# USB.net
KiCad netlist of a schematic drawn in Altium Designer
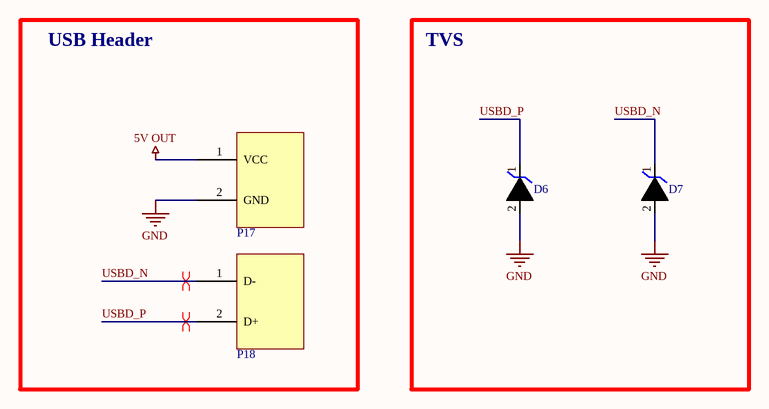
[diagram p0: USB.SchDoc]

(export (version "E")
  (design (tool "Eeschema 10.0.6"))
  (components
    (comp (ref "D6")
      (value "TVS")
      (footprint "TVS DIODE")
      (description "Schematic for TVS diode")
      (libsource (lib "Lib") (part "TVS Diode"))
    )
    (comp (ref "D7")
      (value "TVS")
      (footprint "TVS DIODE")
      (description "Schematic for TVS diode")
      (libsource (lib "Lib") (part "TVS Diode"))
    )
    (comp (ref "P17")
      (value "2-Pin Header")
      (footprint "WR-TBL 322 2H")
      (description "322 series 2 pin header")
      (libsource (lib "Lib") (part "322-2H"))
    )
    (comp (ref "P18")
      (value "2-Pin Header")
      (footprint "WR-TBL 322 2H")
      (description "322 series 2 pin header")
      (libsource (lib "Lib") (part "322-2H"))
    )
  )
  (nets
    (net (code "1") (name "/USBD_N") (class "Default")
      (node (ref "D7") (pin "1") (pinfunction "1_1") (pintype "passive"))
      (node (ref "P18") (pin "1") (pinfunction "VCC_1") (pintype "passive"))
    )
    (net (code "2") (name "/USBD_P") (class "Default")
      (node (ref "D6") (pin "1") (pinfunction "1_1") (pintype "passive"))
      (node (ref "P18") (pin "2") (pinfunction "GND_2") (pintype "passive"))
    )
    (net (code "3") (name "5V OUT") (class "Default")
      (node (ref "P17") (pin "1") (pinfunction "VCC_1") (pintype "passive"))
    )
    (net (code "4") (name "GND") (class "Default")
      (node (ref "D6") (pin "2") (pinfunction "2_2") (pintype "passive"))
      (node (ref "D7") (pin "2") (pinfunction "2_2") (pintype "passive"))
      (node (ref "P17") (pin "2") (pinfunction "GND_2") (pintype "passive"))
    )
  )
)
